# SwirlsV1_1.net
KiCad netlist of a schematic drawn in EAGLE
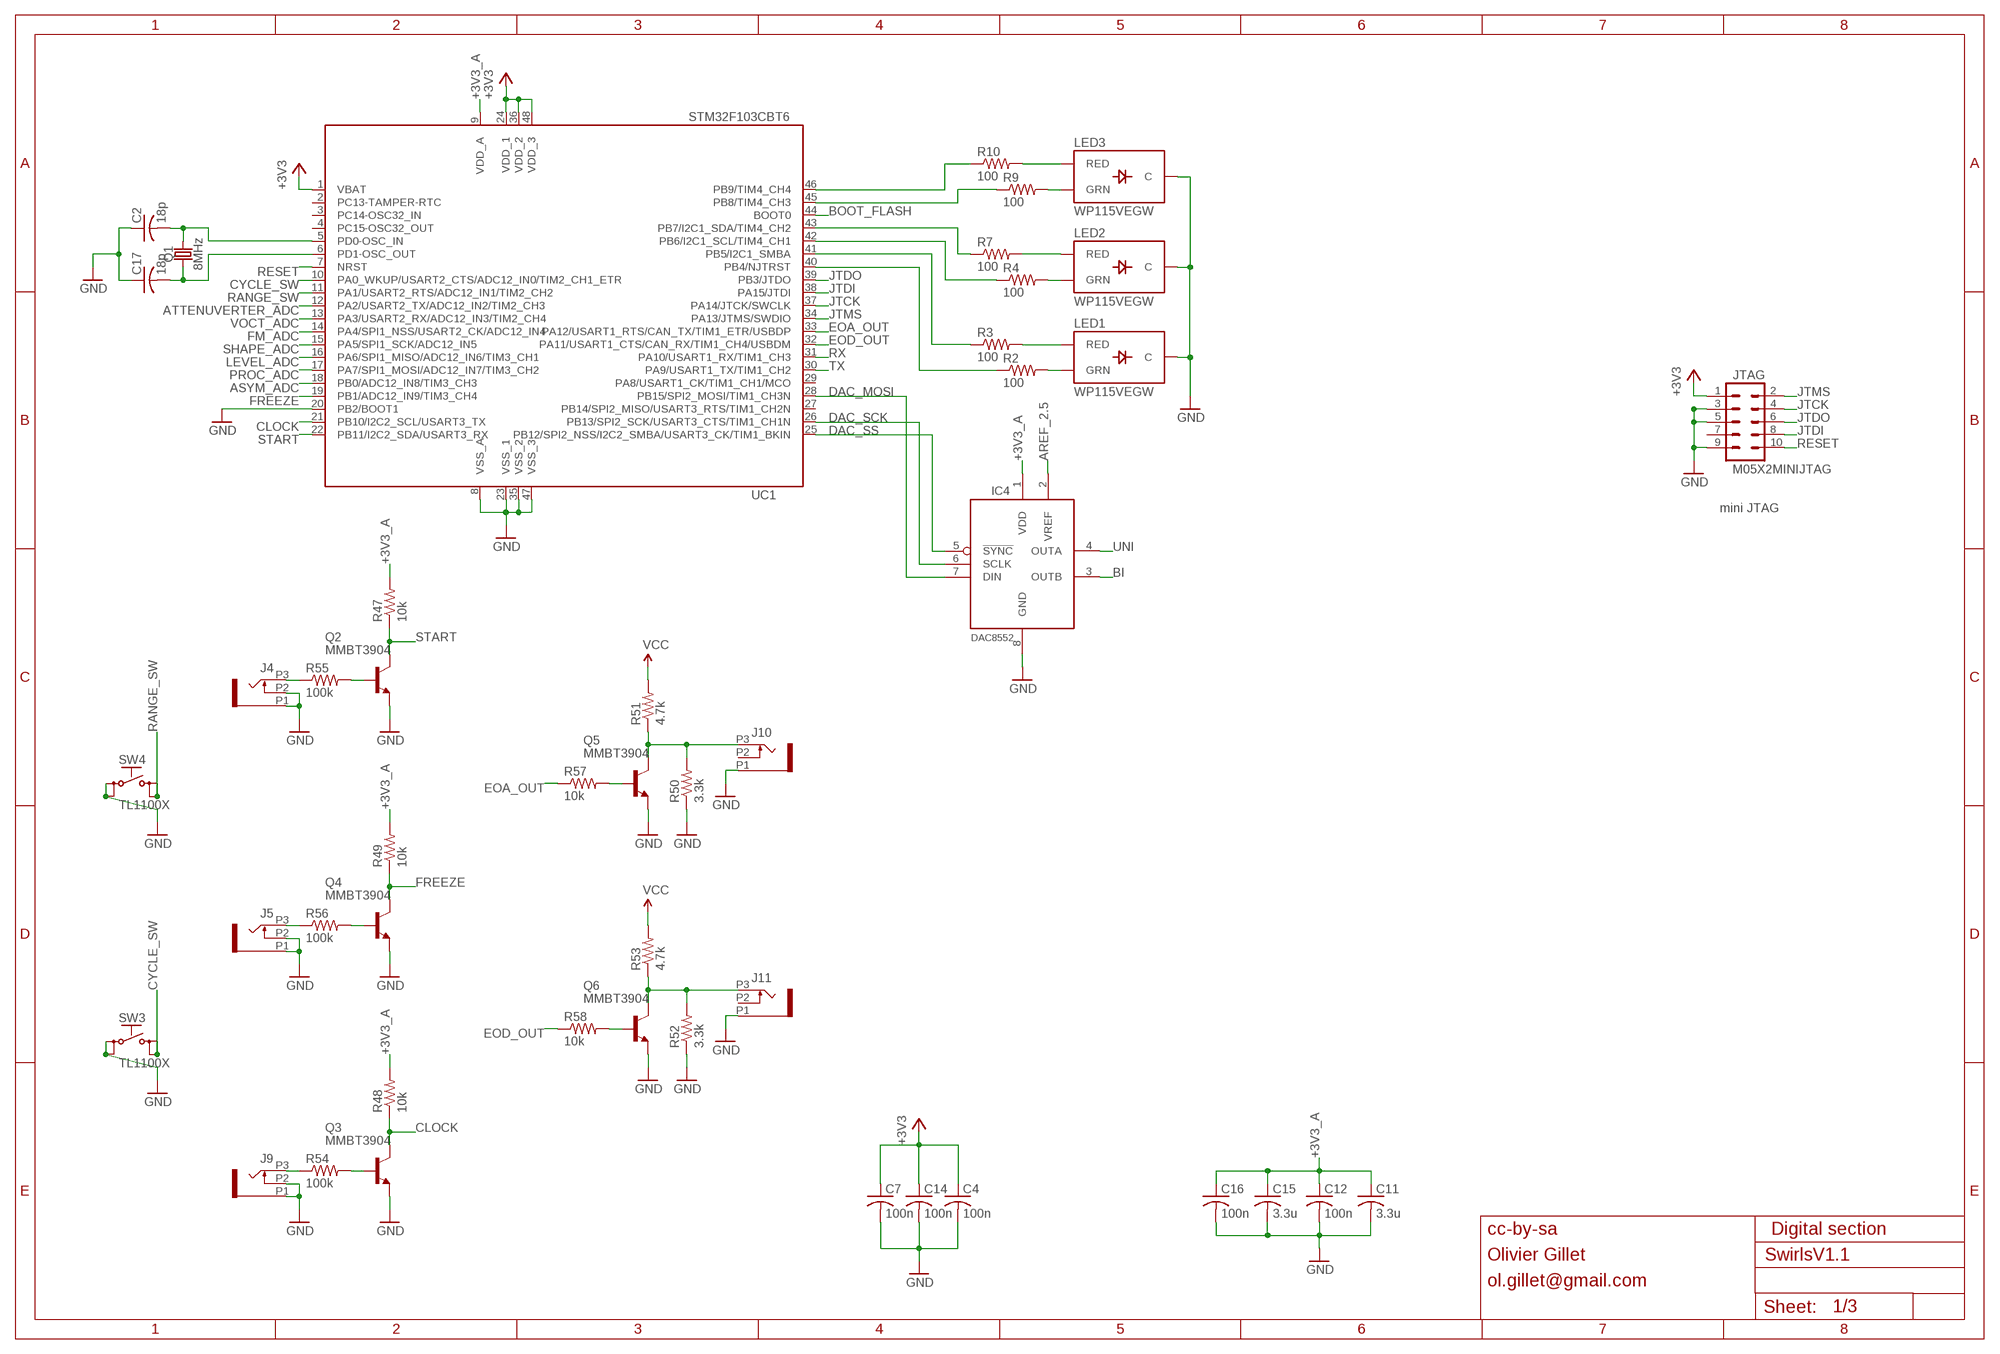
[diagram p0: schematic, sheet 1]
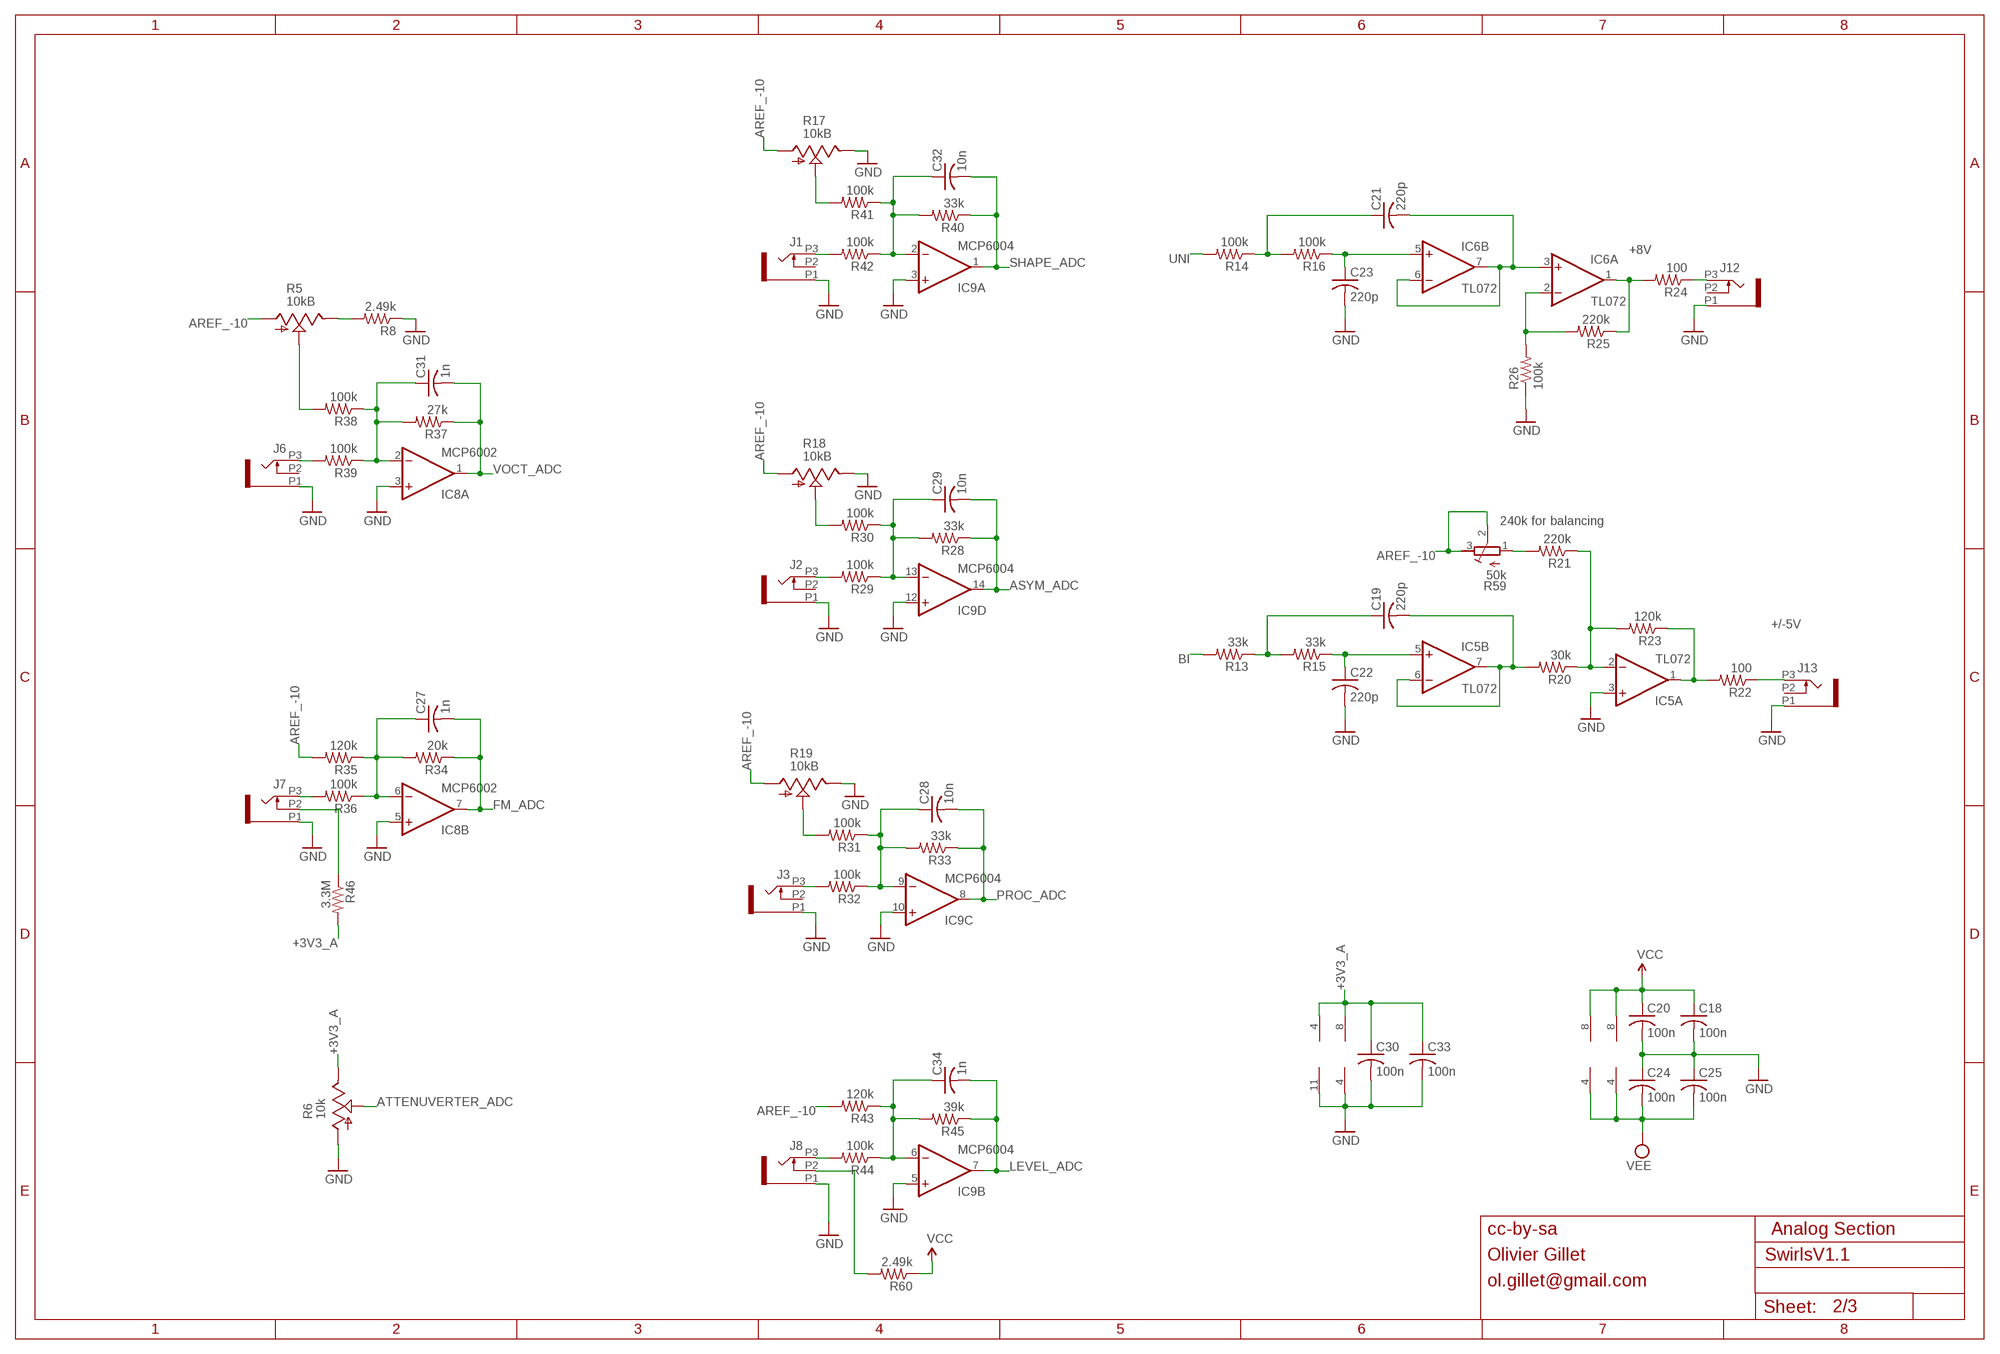
[diagram p1: schematic, sheet 2]
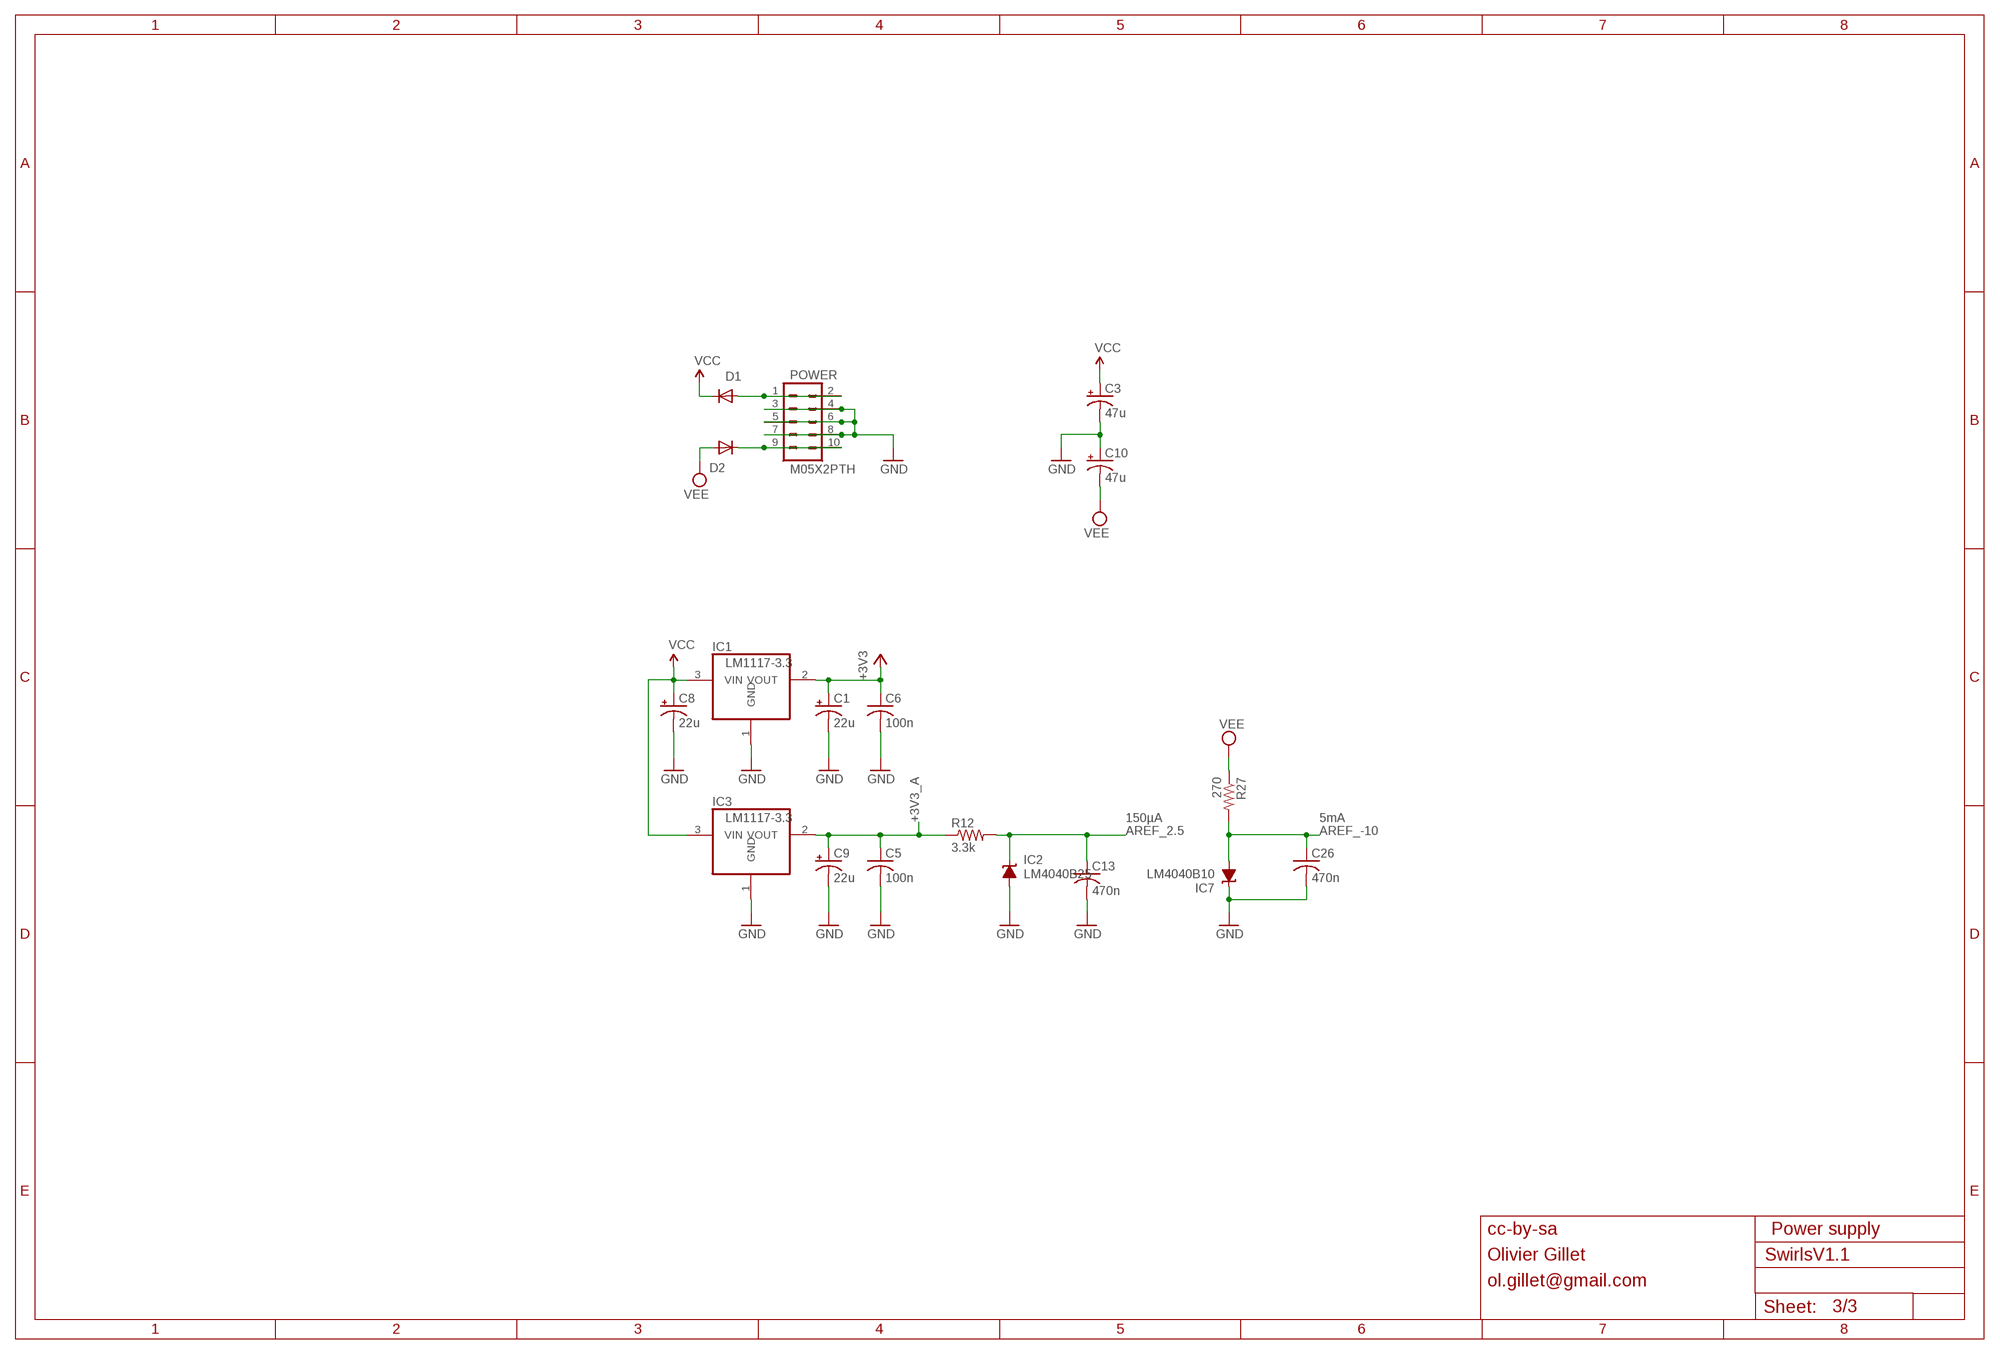
[diagram p2: schematic, sheet 3]

(export (version "E")
  (design (tool "Eeschema 10.0.6"))
  (components
    (comp (ref "C1")
      (value "22u")
      (footprint "eagle-import:PANASONIC_C")
      (libsource (lib "eagle-import") (part "CPOL-USC"))
    )
    (comp (ref "C3")
      (value "47u")
      (footprint "eagle-import:PANASONIC_D")
      (libsource (lib "eagle-import") (part "CPOL-USD"))
    )
    (comp (ref "C5")
      (value "100n")
      (footprint "eagle-import:C0603")
      (libsource (lib "eagle-import") (part "C-USC0603"))
    )
    (comp (ref "C6")
      (value "100n")
      (footprint "eagle-import:C0603")
      (libsource (lib "eagle-import") (part "C-USC0603"))
    )
    (comp (ref "C8")
      (value "22u")
      (footprint "eagle-import:PANASONIC_C")
      (libsource (lib "eagle-import") (part "CPOL-USC"))
    )
    (comp (ref "C9")
      (value "22u")
      (footprint "eagle-import:PANASONIC_C")
      (libsource (lib "eagle-import") (part "CPOL-USC"))
    )
    (comp (ref "C10")
      (value "47u")
      (footprint "eagle-import:PANASONIC_D")
      (libsource (lib "eagle-import") (part "CPOL-USD"))
    )
    (comp (ref "C13")
      (value "470n")
      (footprint "eagle-import:C0603")
      (libsource (lib "eagle-import") (part "C-USC0603"))
    )
    (comp (ref "C26")
      (value "470n")
      (footprint "eagle-import:C0603")
      (libsource (lib "eagle-import") (part "C-USC0603"))
    )
    (comp (ref "D1")
      (value "1N5819HW")
      (footprint "eagle-import:SOD123")
      (libsource (lib "eagle-import") (part "DIODE-SOD123"))
    )
    (comp (ref "D2")
      (value "1N5819HW")
      (footprint "eagle-import:SOD123")
      (libsource (lib "eagle-import") (part "DIODE-SOD123"))
    )
    (comp (ref "IC1")
      (value "LM1117-3.3")
      (footprint "eagle-import:SOT223")
      (libsource (lib "eagle-import") (part "REG1117"))
    )
    (comp (ref "IC2")
      (value "LM4040B25")
      (footprint "eagle-import:DBZ_R-PDSO-G3")
      (libsource (lib "eagle-import") (part "LM4041DBZB12"))
    )
    (comp (ref "IC3")
      (value "LM1117-3.3")
      (footprint "eagle-import:SOT223")
      (libsource (lib "eagle-import") (part "REG1117"))
    )
    (comp (ref "IC7")
      (value "LM4040B10")
      (footprint "eagle-import:DBZ_R-PDSO-G3")
      (libsource (lib "eagle-import") (part "LM4041DBZB12"))
    )
    (comp (ref "POWER")
      (value "M05X2PTH")
      (footprint "eagle-import:AVR_ICSP")
      (libsource (lib "eagle-import") (part "M05X2PTH"))
    )
    (comp (ref "R12")
      (value "3.3k")
      (footprint "eagle-import:R0603")
      (libsource (lib "eagle-import") (part "R-US_R0603"))
    )
    (comp (ref "R27")
      (value "270")
      (footprint "eagle-import:R0603")
      (libsource (lib "eagle-import") (part "R-US_R0603"))
    )
    (comp (ref "C18")
      (value "100n")
      (footprint "eagle-import:C0603")
      (libsource (lib "eagle-import") (part "C-USC0603"))
    )
    (comp (ref "C19")
      (value "220p")
      (footprint "eagle-import:C0603")
      (libsource (lib "eagle-import") (part "C-USC0603"))
    )
    (comp (ref "C20")
      (value "100n")
      (footprint "eagle-import:C0603")
      (libsource (lib "eagle-import") (part "C-USC0603"))
    )
    (comp (ref "C21")
      (value "220p")
      (footprint "eagle-import:C0603")
      (libsource (lib "eagle-import") (part "C-USC0603"))
    )
    (comp (ref "C22")
      (value "220p")
      (footprint "eagle-import:C0603")
      (libsource (lib "eagle-import") (part "C-USC0603"))
    )
    (comp (ref "C23")
      (value "220p")
      (footprint "eagle-import:C0603")
      (libsource (lib "eagle-import") (part "C-USC0603"))
    )
    (comp (ref "C24")
      (value "100n")
      (footprint "eagle-import:C0603")
      (libsource (lib "eagle-import") (part "C-USC0603"))
    )
    (comp (ref "C25")
      (value "100n")
      (footprint "eagle-import:C0603")
      (libsource (lib "eagle-import") (part "C-USC0603"))
    )
    (comp (ref "C27")
      (value "1n")
      (footprint "eagle-import:C0603")
      (libsource (lib "eagle-import") (part "C-USC0603"))
    )
    (comp (ref "C28")
      (value "10n")
      (footprint "eagle-import:C0603")
      (libsource (lib "eagle-import") (part "C-USC0603"))
    )
    (comp (ref "C29")
      (value "10n")
      (footprint "eagle-import:C0603")
      (libsource (lib "eagle-import") (part "C-USC0603"))
    )
    (comp (ref "C30")
      (value "100n")
      (footprint "eagle-import:C0603")
      (libsource (lib "eagle-import") (part "C-USC0603"))
    )
    (comp (ref "C31")
      (value "1n")
      (footprint "eagle-import:C0603")
      (libsource (lib "eagle-import") (part "C-USC0603"))
    )
    (comp (ref "C32")
      (value "10n")
      (footprint "eagle-import:C0603")
      (libsource (lib "eagle-import") (part "C-USC0603"))
    )
    (comp (ref "C33")
      (value "100n")
      (footprint "eagle-import:C0603")
      (libsource (lib "eagle-import") (part "C-USC0603"))
    )
    (comp (ref "C34")
      (value "1n")
      (footprint "eagle-import:C0603")
      (libsource (lib "eagle-import") (part "C-USC0603"))
    )
    (comp (ref "IC5")
      (value "TL072")
      (footprint "eagle-import:TSSOP-8")
      (libsource (lib "eagle-import") (part "TL072TSSOP"))
    )
    (comp (ref "IC6")
      (value "TL072")
      (footprint "eagle-import:TSSOP-8")
      (libsource (lib "eagle-import") (part "TL072TSSOP"))
    )
    (comp (ref "IC8")
      (value "MCP6002")
      (footprint "eagle-import:SO08")
      (libsource (lib "eagle-import") (part "TL072D"))
    )
    (comp (ref "IC9")
      (value "MCP6004")
      (footprint "eagle-import:TSSOP14")
      (libsource (lib "eagle-import") (part "MCP6004ST"))
    )
    (comp (ref "J1")
      (value "PJ301_GUI6")
      (footprint "eagle-import:OG-PJ301_VARIATIONS_WQP_PJ_301M6")
      (libsource (lib "eagle-import") (part "PJ301_GUI6"))
    )
    (comp (ref "J2")
      (value "PJ301_GUI6")
      (footprint "eagle-import:OG-PJ301_VARIATIONS_WQP_PJ_301M6")
      (libsource (lib "eagle-import") (part "PJ301_GUI6"))
    )
    (comp (ref "J3")
      (value "PJ301_GUI6")
      (footprint "eagle-import:OG-PJ301_VARIATIONS_WQP_PJ_301M6")
      (libsource (lib "eagle-import") (part "PJ301_GUI6"))
    )
    (comp (ref "J6")
      (value "PJ301_GUI6")
      (footprint "eagle-import:OG-PJ301_VARIATIONS_WQP_PJ_301M6")
      (libsource (lib "eagle-import") (part "PJ301_GUI6"))
    )
    (comp (ref "J7")
      (value "PJ301_GUI6")
      (footprint "eagle-import:OG-PJ301_VARIATIONS_WQP_PJ_301M6")
      (libsource (lib "eagle-import") (part "PJ301_GUI6"))
    )
    (comp (ref "J8")
      (value "PJ301_GUI6")
      (footprint "eagle-import:OG-PJ301_VARIATIONS_WQP_PJ_301M6")
      (libsource (lib "eagle-import") (part "PJ301_GUI6"))
    )
    (comp (ref "J12")
      (value "PJ301_GUI6")
      (footprint "eagle-import:OG-PJ301_VARIATIONS_WQP_PJ_301M6")
      (libsource (lib "eagle-import") (part "PJ301_GUI6"))
    )
    (comp (ref "J13")
      (value "PJ301_GUI6")
      (footprint "eagle-import:OG-PJ301_VARIATIONS_WQP_PJ_301M6")
      (libsource (lib "eagle-import") (part "PJ301_GUI6"))
    )
    (comp (ref "R5")
      (value "10kB")
      (footprint "eagle-import:ALPS_POT_VERTICAL_PS")
      (libsource (lib "eagle-import") (part "POT_USVERTICAL_PS"))
    )
    (comp (ref "R6")
      (value "10k")
      (footprint "eagle-import:TALLTRIMMER")
      (libsource (lib "eagle-import") (part "POT-ALPS_POT_US"))
    )
    (comp (ref "R8")
      (value "2.49k")
      (footprint "eagle-import:R0603")
      (libsource (lib "eagle-import") (part "R-US_R0603"))
    )
    (comp (ref "R13")
      (value "33k")
      (footprint "eagle-import:R0603")
      (libsource (lib "eagle-import") (part "R-US_R0603"))
    )
    (comp (ref "R14")
      (value "100k")
      (footprint "eagle-import:R0603")
      (libsource (lib "eagle-import") (part "R-US_R0603"))
    )
    (comp (ref "R15")
      (value "33k")
      (footprint "eagle-import:R0603")
      (libsource (lib "eagle-import") (part "R-US_R0603"))
    )
    (comp (ref "R16")
      (value "100k")
      (footprint "eagle-import:R0603")
      (libsource (lib "eagle-import") (part "R-US_R0603"))
    )
    (comp (ref "R17")
      (value "10kB")
      (footprint "eagle-import:TALLTRIMMER")
      (libsource (lib "eagle-import") (part "POT-ALPS_POT_US"))
    )
    (comp (ref "R18")
      (value "10kB")
      (footprint "eagle-import:TALLTRIMMER")
      (libsource (lib "eagle-import") (part "POT-ALPS_POT_US"))
    )
    (comp (ref "R19")
      (value "10kB")
      (footprint "eagle-import:TALLTRIMMER")
      (libsource (lib "eagle-import") (part "POT-ALPS_POT_US"))
    )
    (comp (ref "R20")
      (value "30k")
      (footprint "eagle-import:R0603")
      (libsource (lib "eagle-import") (part "R-US_R0603"))
    )
    (comp (ref "R21")
      (value "220k")
      (footprint "eagle-import:R0603")
      (libsource (lib "eagle-import") (part "R-US_R0603"))
    )
    (comp (ref "R22")
      (value "100")
      (footprint "eagle-import:R0603")
      (libsource (lib "eagle-import") (part "R-US_R0603"))
    )
    (comp (ref "R23")
      (value "120k")
      (footprint "eagle-import:R0603")
      (libsource (lib "eagle-import") (part "R-US_R0603"))
    )
    (comp (ref "R24")
      (value "100")
      (footprint "eagle-import:R0603")
      (libsource (lib "eagle-import") (part "R-US_R0603"))
    )
    (comp (ref "R25")
      (value "220k")
      (footprint "eagle-import:R0603")
      (libsource (lib "eagle-import") (part "R-US_R0603"))
    )
    (comp (ref "R26")
      (value "100k")
      (footprint "eagle-import:R0603")
      (libsource (lib "eagle-import") (part "R-US_R0603"))
    )
    (comp (ref "R28")
      (value "33k")
      (footprint "eagle-import:R0603")
      (libsource (lib "eagle-import") (part "R-US_R0603"))
    )
    (comp (ref "R29")
      (value "100k")
      (footprint "eagle-import:R0603")
      (libsource (lib "eagle-import") (part "R-US_R0603"))
    )
    (comp (ref "R30")
      (value "100k")
      (footprint "eagle-import:R0603")
      (libsource (lib "eagle-import") (part "R-US_R0603"))
    )
    (comp (ref "R31")
      (value "100k")
      (footprint "eagle-import:R0603")
      (libsource (lib "eagle-import") (part "R-US_R0603"))
    )
    (comp (ref "R32")
      (value "100k")
      (footprint "eagle-import:R0603")
      (libsource (lib "eagle-import") (part "R-US_R0603"))
    )
    (comp (ref "R33")
      (value "33k")
      (footprint "eagle-import:R0603")
      (libsource (lib "eagle-import") (part "R-US_R0603"))
    )
    (comp (ref "R34")
      (value "20k")
      (footprint "eagle-import:R0603")
      (libsource (lib "eagle-import") (part "R-US_R0603"))
    )
    (comp (ref "R35")
      (value "120k")
      (footprint "eagle-import:R0603")
      (libsource (lib "eagle-import") (part "R-US_R0603"))
    )
    (comp (ref "R36")
      (value "100k")
      (footprint "eagle-import:R0603")
      (libsource (lib "eagle-import") (part "R-US_R0603"))
    )
    (comp (ref "R37")
      (value "27k")
      (footprint "eagle-import:R0603")
      (libsource (lib "eagle-import") (part "R-US_R0603"))
    )
    (comp (ref "R38")
      (value "100k")
      (footprint "eagle-import:R0603")
      (libsource (lib "eagle-import") (part "R-US_R0603"))
    )
    (comp (ref "R39")
      (value "100k")
      (footprint "eagle-import:R0603")
      (libsource (lib "eagle-import") (part "R-US_R0603"))
    )
    (comp (ref "R40")
      (value "33k")
      (footprint "eagle-import:R0603")
      (libsource (lib "eagle-import") (part "R-US_R0603"))
    )
    (comp (ref "R41")
      (value "100k")
      (footprint "eagle-import:R0603")
      (libsource (lib "eagle-import") (part "R-US_R0603"))
    )
    (comp (ref "R42")
      (value "100k")
      (footprint "eagle-import:R0603")
      (libsource (lib "eagle-import") (part "R-US_R0603"))
    )
    (comp (ref "R43")
      (value "120k")
      (footprint "eagle-import:R0603")
      (libsource (lib "eagle-import") (part "R-US_R0603"))
    )
    (comp (ref "R44")
      (value "100k")
      (footprint "eagle-import:R0603")
      (libsource (lib "eagle-import") (part "R-US_R0603"))
    )
    (comp (ref "R45")
      (value "39k")
      (footprint "eagle-import:R0603")
      (libsource (lib "eagle-import") (part "R-US_R0603"))
    )
    (comp (ref "R46")
      (value "3.3M")
      (footprint "eagle-import:R0603")
      (libsource (lib "eagle-import") (part "R-US_R0603"))
    )
    (comp (ref "R59")
      (value "50k")
      (footprint "eagle-import:RTRIM3296W")
      (libsource (lib "eagle-import") (part "R-TRIMM3296W"))
    )
    (comp (ref "R60")
      (value "2.49k")
      (footprint "eagle-import:R0805")
      (libsource (lib "eagle-import") (part "R-US_R0805"))
    )
    (comp (ref "C2")
      (value "18p")
      (footprint "eagle-import:C0603")
      (libsource (lib "eagle-import") (part "C-USC0603"))
    )
    (comp (ref "C4")
      (value "100n")
      (footprint "eagle-import:C0603")
      (libsource (lib "eagle-import") (part "C-USC0603"))
    )
    (comp (ref "C7")
      (value "100n")
      (footprint "eagle-import:C0603")
      (libsource (lib "eagle-import") (part "C-USC0603"))
    )
    (comp (ref "C11")
      (value "3.3u")
      (footprint "eagle-import:C0603")
      (libsource (lib "eagle-import") (part "C-USC0603"))
    )
    (comp (ref "C12")
      (value "100n")
      (footprint "eagle-import:C0603")
      (libsource (lib "eagle-import") (part "C-USC0603"))
    )
    (comp (ref "C14")
      (value "100n")
      (footprint "eagle-import:C0603")
      (libsource (lib "eagle-import") (part "C-USC0603"))
    )
    (comp (ref "C15")
      (value "3.3u")
      (footprint "eagle-import:C0603")
      (libsource (lib "eagle-import") (part "C-USC0603"))
    )
    (comp (ref "C16")
      (value "100n")
      (footprint "eagle-import:C0603")
      (libsource (lib "eagle-import") (part "C-USC0603"))
    )
    (comp (ref "C17")
      (value "18p")
      (footprint "eagle-import:C0603")
      (libsource (lib "eagle-import") (part "C-USC0603"))
    )
    (comp (ref "IC4")
      (value "DAC8552")
      (footprint "eagle-import:MSOP-8")
      (libsource (lib "eagle-import") (part "DAC8552"))
    )
    (comp (ref "J4")
      (value "PJ301_GUI6")
      (footprint "eagle-import:OG-PJ301_VARIATIONS_WQP_PJ_301M6")
      (libsource (lib "eagle-import") (part "PJ301_GUI6"))
    )
    (comp (ref "J5")
      (value "PJ301_GUI6")
      (footprint "eagle-import:OG-PJ301_VARIATIONS_WQP_PJ_301M6")
      (libsource (lib "eagle-import") (part "PJ301_GUI6"))
    )
    (comp (ref "J9")
      (value "PJ301_GUI6")
      (footprint "eagle-import:OG-PJ301_VARIATIONS_WQP_PJ_301M6")
      (libsource (lib "eagle-import") (part "PJ301_GUI6"))
    )
    (comp (ref "J10")
      (value "PJ301_GUI6")
      (footprint "eagle-import:OG-PJ301_VARIATIONS_WQP_PJ_301M6")
      (libsource (lib "eagle-import") (part "PJ301_GUI6"))
    )
    (comp (ref "J11")
      (value "PJ301_GUI6")
      (footprint "eagle-import:OG-PJ301_VARIATIONS_WQP_PJ_301M6")
      (libsource (lib "eagle-import") (part "PJ301_GUI6"))
    )
    (comp (ref "JTAG")
      (value "M05X2MINIJTAG")
      (footprint "eagle-import:2X5-1.27")
      (libsource (lib "eagle-import") (part "M05X2MINIJTAG"))
    )
    (comp (ref "LED1")
      (value "WP115VEGW")
      (footprint "eagle-import:LED-BICOLOR-THROUGHHOLE")
      (libsource (lib "eagle-import") (part "LED-BICOLOR-THROUGHHOLE"))
    )
    (comp (ref "LED2")
      (value "WP115VEGW")
      (footprint "eagle-import:LED-BICOLOR-THROUGHHOLE")
      (libsource (lib "eagle-import") (part "LED-BICOLOR-THROUGHHOLE"))
    )
    (comp (ref "LED3")
      (value "WP115VEGW")
      (footprint "eagle-import:LED-BICOLOR-THROUGHHOLE")
      (libsource (lib "eagle-import") (part "LED-BICOLOR-THROUGHHOLE"))
    )
    (comp (ref "Q1")
      (value "8MHz")
      (footprint "eagle-import:HC49UP")
      (libsource (lib "eagle-import") (part "CRYSTAL-8MHZSMD-HC49UP"))
    )
    (comp (ref "Q2")
      (value "MMBT3904")
      (footprint "eagle-import:SOT23-BEC")
      (libsource (lib "eagle-import") (part "-NPN-SOT23-BECMMBT3904LT1"))
    )
    (comp (ref "Q3")
      (value "MMBT3904")
      (footprint "eagle-import:SOT23-BEC")
      (libsource (lib "eagle-import") (part "-NPN-SOT23-BECMMBT3904LT1"))
    )
    (comp (ref "Q4")
      (value "MMBT3904")
      (footprint "eagle-import:SOT23-BEC")
      (libsource (lib "eagle-import") (part "-NPN-SOT23-BECMMBT3904LT1"))
    )
    (comp (ref "Q5")
      (value "MMBT3904")
      (footprint "eagle-import:SOT23-BEC")
      (libsource (lib "eagle-import") (part "-NPN-SOT23-BECMMBT3904LT1"))
    )
    (comp (ref "Q6")
      (value "MMBT3904")
      (footprint "eagle-import:SOT23-BEC")
      (libsource (lib "eagle-import") (part "-NPN-SOT23-BECMMBT3904LT1"))
    )
    (comp (ref "R2")
      (value "100")
      (footprint "eagle-import:R0603")
      (libsource (lib "eagle-import") (part "R-US_R0603"))
    )
    (comp (ref "R3")
      (value "100")
      (footprint "eagle-import:R0603")
      (libsource (lib "eagle-import") (part "R-US_R0603"))
    )
    (comp (ref "R4")
      (value "100")
      (footprint "eagle-import:R0603")
      (libsource (lib "eagle-import") (part "R-US_R0603"))
    )
    (comp (ref "R7")
      (value "100")
      (footprint "eagle-import:R0603")
      (libsource (lib "eagle-import") (part "R-US_R0603"))
    )
    (comp (ref "R9")
      (value "100")
      (footprint "eagle-import:R0603")
      (libsource (lib "eagle-import") (part "R-US_R0603"))
    )
    (comp (ref "R10")
      (value "100")
      (footprint "eagle-import:R0603")
      (libsource (lib "eagle-import") (part "R-US_R0603"))
    )
    (comp (ref "R47")
      (value "10k")
      (footprint "eagle-import:R0603")
      (libsource (lib "eagle-import") (part "R-US_R0603"))
    )
    (comp (ref "R48")
      (value "10k")
      (footprint "eagle-import:R0603")
      (libsource (lib "eagle-import") (part "R-US_R0603"))
    )
    (comp (ref "R49")
      (value "10k")
      (footprint "eagle-import:R0603")
      (libsource (lib "eagle-import") (part "R-US_R0603"))
    )
    (comp (ref "R50")
      (value "3.3k")
      (footprint "eagle-import:R0603")
      (libsource (lib "eagle-import") (part "R-US_R0603"))
    )
    (comp (ref "R51")
      (value "4.7k")
      (footprint "eagle-import:R0603")
      (libsource (lib "eagle-import") (part "R-US_R0603"))
    )
    (comp (ref "R52")
      (value "3.3k")
      (footprint "eagle-import:R0603")
      (libsource (lib "eagle-import") (part "R-US_R0603"))
    )
    (comp (ref "R53")
      (value "4.7k")
      (footprint "eagle-import:R0603")
      (libsource (lib "eagle-import") (part "R-US_R0603"))
    )
    (comp (ref "R54")
      (value "100k")
      (footprint "eagle-import:R0603")
      (libsource (lib "eagle-import") (part "R-US_R0603"))
    )
    (comp (ref "R55")
      (value "100k")
      (footprint "eagle-import:R0603")
      (libsource (lib "eagle-import") (part "R-US_R0603"))
    )
    (comp (ref "R56")
      (value "100k")
      (footprint "eagle-import:R0603")
      (libsource (lib "eagle-import") (part "R-US_R0603"))
    )
    (comp (ref "R57")
      (value "10k")
      (footprint "eagle-import:R0603")
      (libsource (lib "eagle-import") (part "R-US_R0603"))
    )
    (comp (ref "R58")
      (value "10k")
      (footprint "eagle-import:R0603")
      (libsource (lib "eagle-import") (part "R-US_R0603"))
    )
    (comp (ref "SW3")
      (value "TL1100X")
      (footprint "eagle-import:TL1100X")
      (libsource (lib "eagle-import") (part "TL1100X"))
    )
    (comp (ref "SW4")
      (value "TL1100X")
      (footprint "eagle-import:TL1100X")
      (libsource (lib "eagle-import") (part "TL1100X"))
    )
    (comp (ref "UC1")
      (value "STM32F103CBT6")
      (footprint "eagle-import:LQFP48")
      (libsource (lib "eagle-import") (part "STM32F103CB"))
    )
  )
  (nets
    (net (code "1") (name "+3V3") (class "Default")
      (node (ref "C1") (pin "+") (pinfunction "+_+") (pintype "passive"))
      (node (ref "C14") (pin "1") (pinfunction "1_1") (pintype "passive"))
      (node (ref "C4") (pin "1") (pinfunction "1_1") (pintype "passive"))
      (node (ref "C6") (pin "1") (pinfunction "1_1") (pintype "passive"))
      (node (ref "C7") (pin "1") (pinfunction "1_1") (pintype "passive"))
      (node (ref "IC1") (pin "2") (pinfunction "VOUT_2") (pintype "output"))
      (node (ref "JTAG") (pin "1") (pinfunction "1_1") (pintype "passive"))
      (node (ref "UC1") (pin "1") (pinfunction "VBAT_1") (pintype "power_in"))
      (node (ref "UC1") (pin "24") (pinfunction "VDD_1_24") (pintype "power_in"))
      (node (ref "UC1") (pin "36") (pinfunction "VDD_2_36") (pintype "power_in"))
      (node (ref "UC1") (pin "48") (pinfunction "VDD_3_48") (pintype "power_in"))
    )
    (net (code "2") (name "+3V3_A") (class "Default")
      (node (ref "C11") (pin "1") (pinfunction "1_1") (pintype "passive"))
      (node (ref "C12") (pin "1") (pinfunction "1_1") (pintype "passive"))
      (node (ref "C15") (pin "1") (pinfunction "1_1") (pintype "passive"))
      (node (ref "C16") (pin "1") (pinfunction "1_1") (pintype "passive"))
      (node (ref "C30") (pin "1") (pinfunction "1_1") (pintype "passive"))
      (node (ref "C33") (pin "1") (pinfunction "1_1") (pintype "passive"))
      (node (ref "C5") (pin "1") (pinfunction "1_1") (pintype "passive"))
      (node (ref "C9") (pin "+") (pinfunction "+_+") (pintype "passive"))
      (node (ref "IC3") (pin "2") (pinfunction "VOUT_2") (pintype "output"))
      (node (ref "IC4") (pin "1") (pinfunction "VDD_1") (pintype "power_in"))
      (node (ref "IC8") (pin "8") (pinfunction "V+_8") (pintype "power_in"))
      (node (ref "IC9") (pin "4") (pinfunction "V+_4") (pintype "power_in"))
      (node (ref "R12") (pin "1") (pinfunction "1_1") (pintype "passive"))
      (node (ref "R46") (pin "2") (pinfunction "2_2") (pintype "passive"))
      (node (ref "R47") (pin "2") (pinfunction "2_2") (pintype "passive"))
      (node (ref "R48") (pin "2") (pinfunction "2_2") (pintype "passive"))
      (node (ref "R49") (pin "2") (pinfunction "2_2") (pintype "passive"))
      (node (ref "R6") (pin "P$1") (pinfunction "E_P$1") (pintype "passive"))
      (node (ref "UC1") (pin "9") (pinfunction "VDD_A_9") (pintype "power_in"))
    )
    (net (code "3") (name "AREF_-10") (class "Default")
      (node (ref "C26") (pin "1") (pinfunction "1_1") (pintype "passive"))
      (node (ref "IC7") (pin "2") (pinfunction "A_2") (pintype "passive"))
      (node (ref "R17") (pin "P$3") (pinfunction "A_P$3") (pintype "passive"))
      (node (ref "R18") (pin "P$3") (pinfunction "A_P$3") (pintype "passive"))
      (node (ref "R19") (pin "P$3") (pinfunction "A_P$3") (pintype "passive"))
      (node (ref "R27") (pin "2") (pinfunction "2_2") (pintype "passive"))
      (node (ref "R35") (pin "2") (pinfunction "2_2") (pintype "passive"))
      (node (ref "R43") (pin "2") (pinfunction "2_2") (pintype "passive"))
      (node (ref "R5") (pin "P$3") (pinfunction "A_P$3") (pintype "passive"))
      (node (ref "R59") (pin "2") (pinfunction "S_2") (pintype "passive"))
      (node (ref "R59") (pin "3") (pinfunction "E_3") (pintype "passive"))
    )
    (net (code "4") (name "AREF_2.5") (class "Default")
      (node (ref "C13") (pin "1") (pinfunction "1_1") (pintype "passive"))
      (node (ref "IC2") (pin "1") (pinfunction "C_1") (pintype "passive"))
      (node (ref "IC4") (pin "2") (pinfunction "VREF_2") (pintype "power_in"))
      (node (ref "R12") (pin "2") (pinfunction "2_2") (pintype "passive"))
    )
    (net (code "5") (name "ASYM_ADC") (class "Default")
      (node (ref "C29") (pin "2") (pinfunction "2_2") (pintype "passive"))
      (node (ref "IC9") (pin "14") (pinfunction "OUT_14") (pintype "output"))
      (node (ref "R28") (pin "1") (pinfunction "1_1") (pintype "passive"))
      (node (ref "UC1") (pin "18") (pinfunction "PB0/ADC12_IN8/TIM3_CH3_18") (pintype "bidirectional"))
    )
    (net (code "6") (name "ATTENUVERTER_ADC") (class "Default")
      (node (ref "R6") (pin "P$2") (pinfunction "S_P$2") (pintype "passive"))
      (node (ref "UC1") (pin "12") (pinfunction "PA2/USART2_TX/ADC12_IN2/TIM2_CH3_12") (pintype "bidirectional"))
    )
    (net (code "7") (name "BI") (class "Default")
      (node (ref "IC4") (pin "3") (pinfunction "OUTB_3") (pintype "input"))
      (node (ref "R13") (pin "2") (pinfunction "2_2") (pintype "passive"))
    )
    (net (code "8") (name "BOOT_FLASH") (class "Default")
      (node (ref "UC1") (pin "44") (pinfunction "BOOT0_44") (pintype "input"))
    )
    (net (code "9") (name "CLOCK") (class "Default")
      (node (ref "Q3") (pin "C") (pinfunction "C_C") (pintype "passive"))
      (node (ref "R48") (pin "1") (pinfunction "1_1") (pintype "passive"))
      (node (ref "UC1") (pin "21") (pinfunction "PB10/I2C2_SCL/USART3_TX_21") (pintype "input"))
    )
    (net (code "10") (name "CYCLE_SW") (class "Default")
      (node (ref "SW3") (pin "3") (pinfunction "S_3") (pintype "passive"))
      (node (ref "SW3") (pin "4") (pinfunction "S1_4") (pintype "passive"))
      (node (ref "UC1") (pin "10") (pinfunction "PA0_WKUP/USART2_CTS/ADC12_IN0/TIM2_CH1_ETR_10") (pintype "bidirectional"))
    )
    (net (code "11") (name "DAC_MOSI") (class "Default")
      (node (ref "IC4") (pin "7") (pinfunction "DIN_7") (pintype "bidirectional"))
      (node (ref "UC1") (pin "28") (pinfunction "PB15/SPI2_MOSI/TIM1_CH3N_28") (pintype "input"))
    )
    (net (code "12") (name "DAC_SCK") (class "Default")
      (node (ref "IC4") (pin "6") (pinfunction "SCLK_6") (pintype "bidirectional"))
      (node (ref "UC1") (pin "26") (pinfunction "PB13/SPI2_SCK/USART3_CTS/TIM1_CH1N_26") (pintype "input"))
    )
    (net (code "13") (name "DAC_SS") (class "Default")
      (node (ref "IC4") (pin "5") (pinfunction "~{SYNC}_5") (pintype "bidirectional"))
      (node (ref "UC1") (pin "25") (pinfunction "PB12/SPI2_NSS/I2C2_SMBA/USART3_CK/TIM1_BKIN_25") (pintype "input"))
    )
    (net (code "14") (name "EOA_OUT") (class "Default")
      (node (ref "R57") (pin "1") (pinfunction "1_1") (pintype "passive"))
      (node (ref "UC1") (pin "33") (pinfunction "PA12/USART1_RTS/CAN_TX/TIM1_ETR/USBDP_33") (pintype "bidirectional"))
    )
    (net (code "15") (name "EOD_OUT") (class "Default")
      (node (ref "R58") (pin "1") (pinfunction "1_1") (pintype "passive"))
      (node (ref "UC1") (pin "32") (pinfunction "PA11/USART1_CTS/CAN_RX/TIM1_CH4/USBDM_32") (pintype "bidirectional"))
    )
    (net (code "16") (name "FM_ADC") (class "Default")
      (node (ref "C27") (pin "2") (pinfunction "2_2") (pintype "passive"))
      (node (ref "IC8") (pin "7") (pinfunction "OUT_7") (pintype "output"))
      (node (ref "R34") (pin "1") (pinfunction "1_1") (pintype "passive"))
      (node (ref "UC1") (pin "14") (pinfunction "PA4/SPI1_NSS/USART2_CK/ADC12_IN4_14") (pintype "bidirectional"))
    )
    (net (code "17") (name "FREEZE") (class "Default")
      (node (ref "Q4") (pin "C") (pinfunction "C_C") (pintype "passive"))
      (node (ref "R49") (pin "1") (pinfunction "1_1") (pintype "passive"))
      (node (ref "UC1") (pin "19") (pinfunction "PB1/ADC12_IN9/TIM3_CH4_19") (pintype "bidirectional"))
    )
    (net (code "18") (name "GND") (class "Default")
      (node (ref "C1") (pin "-") (pinfunction "-_-") (pintype "passive"))
      (node (ref "C10") (pin "+") (pinfunction "+_+") (pintype "passive"))
      (node (ref "C11") (pin "2") (pinfunction "2_2") (pintype "passive"))
      (node (ref "C12") (pin "2") (pinfunction "2_2") (pintype "passive"))
      (node (ref "C13") (pin "2") (pinfunction "2_2") (pintype "passive"))
      (node (ref "C14") (pin "2") (pinfunction "2_2") (pintype "passive"))
      (node (ref "C15") (pin "2") (pinfunction "2_2") (pintype "passive"))
      (node (ref "C16") (pin "2") (pinfunction "2_2") (pintype "passive"))
      (node (ref "C17") (pin "1") (pinfunction "1_1") (pintype "passive"))
      (node (ref "C18") (pin "2") (pinfunction "2_2") (pintype "passive"))
      (node (ref "C2") (pin "1") (pinfunction "1_1") (pintype "passive"))
      (node (ref "C20") (pin "2") (pinfunction "2_2") (pintype "passive"))
      (node (ref "C22") (pin "2") (pinfunction "2_2") (pintype "passive"))
      (node (ref "C23") (pin "2") (pinfunction "2_2") (pintype "passive"))
      (node (ref "C24") (pin "1") (pinfunction "1_1") (pintype "passive"))
      (node (ref "C25") (pin "1") (pinfunction "1_1") (pintype "passive"))
      (node (ref "C26") (pin "2") (pinfunction "2_2") (pintype "passive"))
      (node (ref "C3") (pin "-") (pinfunction "-_-") (pintype "passive"))
      (node (ref "C30") (pin "2") (pinfunction "2_2") (pintype "passive"))
      (node (ref "C33") (pin "2") (pinfunction "2_2") (pintype "passive"))
      (node (ref "C4") (pin "2") (pinfunction "2_2") (pintype "passive"))
      (node (ref "C5") (pin "2") (pinfunction "2_2") (pintype "passive"))
      (node (ref "C6") (pin "2") (pinfunction "2_2") (pintype "passive"))
      (node (ref "C7") (pin "2") (pinfunction "2_2") (pintype "passive"))
      (node (ref "C8") (pin "-") (pinfunction "-_-") (pintype "passive"))
      (node (ref "C9") (pin "-") (pinfunction "-_-") (pintype "passive"))
      (node (ref "IC1") (pin "1") (pinfunction "GND_1") (pintype "power_in"))
      (node (ref "IC2") (pin "2") (pinfunction "A_2") (pintype "passive"))
      (node (ref "IC3") (pin "1") (pinfunction "GND_1") (pintype "power_in"))
      (node (ref "IC4") (pin "8") (pinfunction "GND_8") (pintype "power_in"))
      (node (ref "IC5") (pin "3") (pinfunction "+IN_3") (pintype "input"))
      (node (ref "IC7") (pin "1") (pinfunction "C_1") (pintype "passive"))
      (node (ref "IC8") (pin "3") (pinfunction "+IN_3") (pintype "input"))
      (node (ref "IC8") (pin "4") (pinfunction "V-_4") (pintype "power_in"))
      (node (ref "IC8") (pin "5") (pinfunction "+IN_5") (pintype "input"))
      (node (ref "IC9") (pin "10") (pinfunction "+IN_10") (pintype "input"))
      (node (ref "IC9") (pin "11") (pinfunction "V-_11") (pintype "power_in"))
      (node (ref "IC9") (pin "12") (pinfunction "+IN_12") (pintype "input"))
      (node (ref "IC9") (pin "3") (pinfunction "+IN_3") (pintype "input"))
      (node (ref "IC9") (pin "5") (pinfunction "+IN_5") (pintype "input"))
      (node (ref "J1") (pin "P1") (pinfunction "1_P1") (pintype "passive"))
      (node (ref "J10") (pin "P1") (pinfunction "1_P1") (pintype "passive"))
      (node (ref "J11") (pin "P1") (pinfunction "1_P1") (pintype "passive"))
      (node (ref "J12") (pin "P1") (pinfunction "1_P1") (pintype "passive"))
      (node (ref "J13") (pin "P1") (pinfunction "1_P1") (pintype "passive"))
      (node (ref "J2") (pin "P1") (pinfunction "1_P1") (pintype "passive"))
      (node (ref "J3") (pin "P1") (pinfunction "1_P1") (pintype "passive"))
      (node (ref "J4") (pin "P1") (pinfunction "1_P1") (pintype "passive"))
      (node (ref "J4") (pin "P2") (pinfunction "2_P2") (pintype "passive"))
      (node (ref "J5") (pin "P1") (pinfunction "1_P1") (pintype "passive"))
      (node (ref "J5") (pin "P2") (pinfunction "2_P2") (pintype "passive"))
      (node (ref "J6") (pin "P1") (pinfunction "1_P1") (pintype "passive"))
      (node (ref "J7") (pin "P1") (pinfunction "1_P1") (pintype "passive"))
      (node (ref "J8") (pin "P1") (pinfunction "1_P1") (pintype "passive"))
      (node (ref "J9") (pin "P1") (pinfunction "1_P1") (pintype "passive"))
      (node (ref "J9") (pin "P2") (pinfunction "2_P2") (pintype "passive"))
      (node (ref "JTAG") (pin "3") (pinfunction "3_3") (pintype "passive"))
      (node (ref "JTAG") (pin "5") (pinfunction "5_5") (pintype "passive"))
      (node (ref "JTAG") (pin "9") (pinfunction "9_9") (pintype "passive"))
      (node (ref "LED1") (pin "2") (pinfunction "C_2") (pintype "bidirectional"))
      (node (ref "LED2") (pin "2") (pinfunction "C_2") (pintype "bidirectional"))
      (node (ref "LED3") (pin "2") (pinfunction "C_2") (pintype "bidirectional"))
      (node (ref "POWER") (pin "3") (pinfunction "3_3") (pintype "passive"))
      (node (ref "POWER") (pin "4") (pinfunction "4_4") (pintype "passive"))
      (node (ref "POWER") (pin "5") (pinfunction "5_5") (pintype "passive"))
      (node (ref "POWER") (pin "6") (pinfunction "6_6") (pintype "passive"))
      (node (ref "POWER") (pin "7") (pinfunction "7_7") (pintype "passive"))
      (node (ref "POWER") (pin "8") (pinfunction "8_8") (pintype "passive"))
      (node (ref "Q2") (pin "E") (pinfunction "E_E") (pintype "passive"))
      (node (ref "Q3") (pin "E") (pinfunction "E_E") (pintype "passive"))
      (node (ref "Q4") (pin "E") (pinfunction "E_E") (pintype "passive"))
      (node (ref "Q5") (pin "E") (pinfunction "E_E") (pintype "passive"))
      (node (ref "Q6") (pin "E") (pinfunction "E_E") (pintype "passive"))
      (node (ref "R17") (pin "P$1") (pinfunction "E_P$1") (pintype "passive"))
      (node (ref "R18") (pin "P$1") (pinfunction "E_P$1") (pintype "passive"))
      (node (ref "R19") (pin "P$1") (pinfunction "E_P$1") (pintype "passive"))
      (node (ref "R26") (pin "1") (pinfunction "1_1") (pintype "passive"))
      (node (ref "R50") (pin "1") (pinfunction "1_1") (pintype "passive"))
      (node (ref "R52") (pin "1") (pinfunction "1_1") (pintype "passive"))
      (node (ref "R6") (pin "P$3") (pinfunction "A_P$3") (pintype "passive"))
      (node (ref "R8") (pin "1") (pinfunction "1_1") (pintype "passive"))
      (node (ref "SW3") (pin "1") (pinfunction "P_1") (pintype "passive"))
      (node (ref "SW3") (pin "2") (pinfunction "P1_2") (pintype "passive"))
      (node (ref "SW4") (pin "1") (pinfunction "P_1") (pintype "passive"))
      (node (ref "SW4") (pin "2") (pinfunction "P1_2") (pintype "passive"))
      (node (ref "UC1") (pin "20") (pinfunction "PB2/BOOT1_20") (pintype "bidirectional"))
      (node (ref "UC1") (pin "23") (pinfunction "VSS_1_23") (pintype "power_in"))
      (node (ref "UC1") (pin "35") (pinfunction "VSS_2_35") (pintype "power_in"))
      (node (ref "UC1") (pin "47") (pinfunction "VSS_3_47") (pintype "power_in"))
      (node (ref "UC1") (pin "8") (pinfunction "VSS_A_8") (pintype "power_in"))
    )
    (net (code "19") (name "JTCK") (class "Default")
      (node (ref "JTAG") (pin "4") (pinfunction "4_4") (pintype "passive"))
      (node (ref "UC1") (pin "37") (pinfunction "PA14/JTCK/SWCLK_37") (pintype "bidirectional"))
    )
    (net (code "20") (name "JTDI") (class "Default")
      (node (ref "JTAG") (pin "8") (pinfunction "8_8") (pintype "passive"))
      (node (ref "UC1") (pin "38") (pinfunction "PA15/JTDI_38") (pintype "bidirectional"))
    )
    (net (code "21") (name "JTDO") (class "Default")
      (node (ref "JTAG") (pin "6") (pinfunction "6_6") (pintype "passive"))
      (node (ref "UC1") (pin "39") (pinfunction "PB3/JTDO_39") (pintype "bidirectional"))
    )
    (net (code "22") (name "JTMS") (class "Default")
      (node (ref "JTAG") (pin "2") (pinfunction "2_2") (pintype "passive"))
      (node (ref "UC1") (pin "34") (pinfunction "PA13/JTMS/SWDIO_34") (pintype "bidirectional"))
    )
    (net (code "23") (name "LEVEL_ADC") (class "Default")
      (node (ref "C34") (pin "2") (pinfunction "2_2") (pintype "passive"))
      (node (ref "IC9") (pin "7") (pinfunction "OUT_7") (pintype "output"))
      (node (ref "R45") (pin "1") (pinfunction "1_1") (pintype "passive"))
      (node (ref "UC1") (pin "16") (pinfunction "PA6/SPI1_MISO/ADC12_IN6/TIM3_CH1_16") (pintype "bidirectional"))
    )
    (net (code "24") (name "Net-(C19-Pad1)") (class "Default")
      (node (ref "C19") (pin "1") (pinfunction "1_1") (pintype "passive"))
      (node (ref "R13") (pin "1") (pinfunction "1_1") (pintype "passive"))
      (node (ref "R15") (pin "2") (pinfunction "2_2") (pintype "passive"))
    )
    (net (code "25") (name "Net-(C21-Pad1)") (class "Default")
      (node (ref "C21") (pin "1") (pinfunction "1_1") (pintype "passive"))
      (node (ref "R14") (pin "1") (pinfunction "1_1") (pintype "passive"))
      (node (ref "R16") (pin "2") (pinfunction "2_2") (pintype "passive"))
    )
    (net (code "26") (name "Net-(D1-PadA)") (class "Default")
      (node (ref "D1") (pin "A") (pinfunction "A_A") (pintype "passive"))
      (node (ref "POWER") (pin "1") (pinfunction "1_1") (pintype "passive"))
      (node (ref "POWER") (pin "2") (pinfunction "2_2") (pintype "passive"))
    )
    (net (code "27") (name "Net-(D2-PadC)") (class "Default")
      (node (ref "D2") (pin "C") (pinfunction "C_C") (pintype "passive"))
      (node (ref "POWER") (pin "10") (pinfunction "10_10") (pintype "passive"))
      (node (ref "POWER") (pin "9") (pinfunction "9_9") (pintype "passive"))
    )
    (net (code "28") (name "Net-(IC5A--IN)") (class "Default")
      (node (ref "IC5") (pin "2") (pinfunction "-IN_2") (pintype "input"))
      (node (ref "R20") (pin "1") (pinfunction "1_1") (pintype "passive"))
      (node (ref "R21") (pin "1") (pinfunction "1_1") (pintype "passive"))
      (node (ref "R23") (pin "2") (pinfunction "2_2") (pintype "passive"))
    )
    (net (code "29") (name "Net-(IC5A-OUT)") (class "Default")
      (node (ref "IC5") (pin "1") (pinfunction "OUT_1") (pintype "output"))
      (node (ref "R22") (pin "2") (pinfunction "2_2") (pintype "passive"))
      (node (ref "R23") (pin "1") (pinfunction "1_1") (pintype "passive"))
    )
    (net (code "30") (name "Net-(IC5B-+IN)") (class "Default")
      (node (ref "C22") (pin "1") (pinfunction "1_1") (pintype "passive"))
      (node (ref "IC5") (pin "5") (pinfunction "+IN_5") (pintype "input"))
      (node (ref "R15") (pin "1") (pinfunction "1_1") (pintype "passive"))
    )
    (net (code "31") (name "Net-(IC5B--IN)") (class "Default")
      (node (ref "C19") (pin "2") (pinfunction "2_2") (pintype "passive"))
      (node (ref "IC5") (pin "6") (pinfunction "-IN_6") (pintype "input"))
      (node (ref "IC5") (pin "7") (pinfunction "OUT_7") (pintype "output"))
      (node (ref "R20") (pin "2") (pinfunction "2_2") (pintype "passive"))
    )
    (net (code "32") (name "Net-(IC6A-+IN)") (class "Default")
      (node (ref "C21") (pin "2") (pinfunction "2_2") (pintype "passive"))
      (node (ref "IC6") (pin "3") (pinfunction "+IN_3") (pintype "input"))
      (node (ref "IC6") (pin "6") (pinfunction "-IN_6") (pintype "input"))
      (node (ref "IC6") (pin "7") (pinfunction "OUT_7") (pintype "output"))
    )
    (net (code "33") (name "Net-(IC6A--IN)") (class "Default")
      (node (ref "IC6") (pin "2") (pinfunction "-IN_2") (pintype "input"))
      (node (ref "R25") (pin "2") (pinfunction "2_2") (pintype "passive"))
      (node (ref "R26") (pin "2") (pinfunction "2_2") (pintype "passive"))
    )
    (net (code "34") (name "Net-(IC6A-OUT)") (class "Default")
      (node (ref "IC6") (pin "1") (pinfunction "OUT_1") (pintype "output"))
      (node (ref "R24") (pin "2") (pinfunction "2_2") (pintype "passive"))
      (node (ref "R25") (pin "1") (pinfunction "1_1") (pintype "passive"))
    )
    (net (code "35") (name "Net-(IC6B-+IN)") (class "Default")
      (node (ref "C23") (pin "1") (pinfunction "1_1") (pintype "passive"))
      (node (ref "IC6") (pin "5") (pinfunction "+IN_5") (pintype "input"))
      (node (ref "R16") (pin "1") (pinfunction "1_1") (pintype "passive"))
    )
    (net (code "36") (name "Net-(IC8A--IN)") (class "Default")
      (node (ref "C31") (pin "1") (pinfunction "1_1") (pintype "passive"))
      (node (ref "IC8") (pin "2") (pinfunction "-IN_2") (pintype "input"))
      (node (ref "R37") (pin "2") (pinfunction "2_2") (pintype "passive"))
      (node (ref "R38") (pin "1") (pinfunction "1_1") (pintype "passive"))
      (node (ref "R39") (pin "1") (pinfunction "1_1") (pintype "passive"))
    )
    (net (code "37") (name "Net-(IC8B--IN)") (class "Default")
      (node (ref "C27") (pin "1") (pinfunction "1_1") (pintype "passive"))
      (node (ref "IC8") (pin "6") (pinfunction "-IN_6") (pintype "input"))
      (node (ref "R34") (pin "2") (pinfunction "2_2") (pintype "passive"))
      (node (ref "R35") (pin "1") (pinfunction "1_1") (pintype "passive"))
      (node (ref "R36") (pin "1") (pinfunction "1_1") (pintype "passive"))
    )
    (net (code "38") (name "Net-(IC9A--IN)") (class "Default")
      (node (ref "C32") (pin "1") (pinfunction "1_1") (pintype "passive"))
      (node (ref "IC9") (pin "2") (pinfunction "-IN_2") (pintype "input"))
      (node (ref "R40") (pin "2") (pinfunction "2_2") (pintype "passive"))
      (node (ref "R41") (pin "1") (pinfunction "1_1") (pintype "passive"))
      (node (ref "R42") (pin "1") (pinfunction "1_1") (pintype "passive"))
    )
    (net (code "39") (name "Net-(IC9B--IN)") (class "Default")
      (node (ref "C34") (pin "1") (pinfunction "1_1") (pintype "passive"))
      (node (ref "IC9") (pin "6") (pinfunction "-IN_6") (pintype "input"))
      (node (ref "R43") (pin "1") (pinfunction "1_1") (pintype "passive"))
      (node (ref "R44") (pin "1") (pinfunction "1_1") (pintype "passive"))
      (node (ref "R45") (pin "2") (pinfunction "2_2") (pintype "passive"))
    )
    (net (code "40") (name "Net-(IC9C--IN)") (class "Default")
      (node (ref "C28") (pin "1") (pinfunction "1_1") (pintype "passive"))
      (node (ref "IC9") (pin "9") (pinfunction "-IN_9") (pintype "input"))
      (node (ref "R31") (pin "1") (pinfunction "1_1") (pintype "passive"))
      (node (ref "R32") (pin "1") (pinfunction "1_1") (pintype "passive"))
      (node (ref "R33") (pin "2") (pinfunction "2_2") (pintype "passive"))
    )
    (net (code "41") (name "Net-(IC9D--IN)") (class "Default")
      (node (ref "C29") (pin "1") (pinfunction "1_1") (pintype "passive"))
      (node (ref "IC9") (pin "13") (pinfunction "-IN_13") (pintype "input"))
      (node (ref "R28") (pin "2") (pinfunction "2_2") (pintype "passive"))
      (node (ref "R29") (pin "1") (pinfunction "1_1") (pintype "passive"))
      (node (ref "R30") (pin "1") (pinfunction "1_1") (pintype "passive"))
    )
    (net (code "42") (name "Net-(J1-3)") (class "Default")
      (node (ref "J1") (pin "P3") (pinfunction "3_P3") (pintype "passive"))
      (node (ref "R42") (pin "2") (pinfunction "2_2") (pintype "passive"))
    )
    (net (code "43") (name "Net-(J2-3)") (class "Default")
      (node (ref "J2") (pin "P3") (pinfunction "3_P3") (pintype "passive"))
      (node (ref "R29") (pin "2") (pinfunction "2_2") (pintype "passive"))
    )
    (net (code "44") (name "Net-(J3-3)") (class "Default")
      (node (ref "J3") (pin "P3") (pinfunction "3_P3") (pintype "passive"))
      (node (ref "R32") (pin "2") (pinfunction "2_2") (pintype "passive"))
    )
    (net (code "45") (name "Net-(J4-3)") (class "Default")
      (node (ref "J4") (pin "P3") (pinfunction "3_P3") (pintype "passive"))
      (node (ref "R55") (pin "1") (pinfunction "1_1") (pintype "passive"))
    )
    (net (code "46") (name "Net-(J5-3)") (class "Default")
      (node (ref "J5") (pin "P3") (pinfunction "3_P3") (pintype "passive"))
      (node (ref "R56") (pin "1") (pinfunction "1_1") (pintype "passive"))
    )
    (net (code "47") (name "Net-(J6-3)") (class "Default")
      (node (ref "J6") (pin "P3") (pinfunction "3_P3") (pintype "passive"))
      (node (ref "R39") (pin "2") (pinfunction "2_2") (pintype "passive"))
    )
    (net (code "48") (name "Net-(J7-2)") (class "Default")
      (node (ref "J7") (pin "P2") (pinfunction "2_P2") (pintype "passive"))
      (node (ref "R46") (pin "1") (pinfunction "1_1") (pintype "passive"))
    )
    (net (code "49") (name "Net-(J7-3)") (class "Default")
      (node (ref "J7") (pin "P3") (pinfunction "3_P3") (pintype "passive"))
      (node (ref "R36") (pin "2") (pinfunction "2_2") (pintype "passive"))
    )
    (net (code "50") (name "Net-(J8-2)") (class "Default")
      (node (ref "J8") (pin "P2") (pinfunction "2_P2") (pintype "passive"))
      (node (ref "R60") (pin "2") (pinfunction "2_2") (pintype "passive"))
    )
    (net (code "51") (name "Net-(J8-3)") (class "Default")
      (node (ref "J8") (pin "P3") (pinfunction "3_P3") (pintype "passive"))
      (node (ref "R44") (pin "2") (pinfunction "2_2") (pintype "passive"))
    )
    (net (code "52") (name "Net-(J9-3)") (class "Default")
      (node (ref "J9") (pin "P3") (pinfunction "3_P3") (pintype "passive"))
      (node (ref "R54") (pin "1") (pinfunction "1_1") (pintype "passive"))
    )
    (net (code "53") (name "Net-(J10-3)") (class "Default")
      (node (ref "J10") (pin "P3") (pinfunction "3_P3") (pintype "passive"))
      (node (ref "Q5") (pin "C") (pinfunction "C_C") (pintype "passive"))
      (node (ref "R50") (pin "2") (pinfunction "2_2") (pintype "passive"))
      (node (ref "R51") (pin "1") (pinfunction "1_1") (pintype "passive"))
    )
    (net (code "54") (name "Net-(J11-3)") (class "Default")
      (node (ref "J11") (pin "P3") (pinfunction "3_P3") (pintype "passive"))
      (node (ref "Q6") (pin "C") (pinfunction "C_C") (pintype "passive"))
      (node (ref "R52") (pin "2") (pinfunction "2_2") (pintype "passive"))
      (node (ref "R53") (pin "1") (pinfunction "1_1") (pintype "passive"))
    )
    (net (code "55") (name "Net-(J12-3)") (class "Default")
      (node (ref "J12") (pin "P3") (pinfunction "3_P3") (pintype "passive"))
      (node (ref "R24") (pin "1") (pinfunction "1_1") (pintype "passive"))
    )
    (net (code "56") (name "Net-(J13-3)") (class "Default")
      (node (ref "J13") (pin "P3") (pinfunction "3_P3") (pintype "passive"))
      (node (ref "R22") (pin "1") (pinfunction "1_1") (pintype "passive"))
    )
    (net (code "57") (name "Net-(LED1-GRN)") (class "Default")
      (node (ref "LED1") (pin "1") (pinfunction "GRN_1") (pintype "bidirectional"))
      (node (ref "R2") (pin "2") (pinfunction "2_2") (pintype "passive"))
    )
    (net (code "58") (name "Net-(LED1-RED)") (class "Default")
      (node (ref "LED1") (pin "3") (pinfunction "RED_3") (pintype "bidirectional"))
      (node (ref "R3") (pin "2") (pinfunction "2_2") (pintype "passive"))
    )
    (net (code "59") (name "Net-(LED2-GRN)") (class "Default")
      (node (ref "LED2") (pin "1") (pinfunction "GRN_1") (pintype "bidirectional"))
      (node (ref "R4") (pin "2") (pinfunction "2_2") (pintype "passive"))
    )
    (net (code "60") (name "Net-(LED2-RED)") (class "Default")
      (node (ref "LED2") (pin "3") (pinfunction "RED_3") (pintype "bidirectional"))
      (node (ref "R7") (pin "2") (pinfunction "2_2") (pintype "passive"))
    )
    (net (code "61") (name "Net-(LED3-GRN)") (class "Default")
      (node (ref "LED3") (pin "1") (pinfunction "GRN_1") (pintype "bidirectional"))
      (node (ref "R9") (pin "2") (pinfunction "2_2") (pintype "passive"))
    )
    (net (code "62") (name "Net-(LED3-RED)") (class "Default")
      (node (ref "LED3") (pin "3") (pinfunction "RED_3") (pintype "bidirectional"))
      (node (ref "R10") (pin "2") (pinfunction "2_2") (pintype "passive"))
    )
    (net (code "63") (name "Net-(Q2-PadB)") (class "Default")
      (node (ref "Q2") (pin "B") (pinfunction "B_B") (pintype "passive"))
      (node (ref "R55") (pin "2") (pinfunction "2_2") (pintype "passive"))
    )
    (net (code "64") (name "Net-(Q3-PadB)") (class "Default")
      (node (ref "Q3") (pin "B") (pinfunction "B_B") (pintype "passive"))
      (node (ref "R54") (pin "2") (pinfunction "2_2") (pintype "passive"))
    )
    (net (code "65") (name "Net-(Q4-PadB)") (class "Default")
      (node (ref "Q4") (pin "B") (pinfunction "B_B") (pintype "passive"))
      (node (ref "R56") (pin "2") (pinfunction "2_2") (pintype "passive"))
    )
    (net (code "66") (name "Net-(Q5-PadB)") (class "Default")
      (node (ref "Q5") (pin "B") (pinfunction "B_B") (pintype "passive"))
      (node (ref "R57") (pin "2") (pinfunction "2_2") (pintype "passive"))
    )
    (net (code "67") (name "Net-(Q6-PadB)") (class "Default")
      (node (ref "Q6") (pin "B") (pinfunction "B_B") (pintype "passive"))
      (node (ref "R58") (pin "2") (pinfunction "2_2") (pintype "passive"))
    )
    (net (code "68") (name "Net-(R5-E)") (class "Default")
      (node (ref "R5") (pin "P$1") (pinfunction "E_P$1") (pintype "passive"))
      (node (ref "R8") (pin "2") (pinfunction "2_2") (pintype "passive"))
    )
    (net (code "69") (name "Net-(R5-S)") (class "Default")
      (node (ref "R38") (pin "2") (pinfunction "2_2") (pintype "passive"))
      (node (ref "R5") (pin "P$2") (pinfunction "S_P$2") (pintype "passive"))
    )
    (net (code "70") (name "Net-(R17-S)") (class "Default")
      (node (ref "R17") (pin "P$2") (pinfunction "S_P$2") (pintype "passive"))
      (node (ref "R41") (pin "2") (pinfunction "2_2") (pintype "passive"))
    )
    (net (code "71") (name "Net-(R18-S)") (class "Default")
      (node (ref "R18") (pin "P$2") (pinfunction "S_P$2") (pintype "passive"))
      (node (ref "R30") (pin "2") (pinfunction "2_2") (pintype "passive"))
    )
    (net (code "72") (name "Net-(R19-S)") (class "Default")
      (node (ref "R19") (pin "P$2") (pinfunction "S_P$2") (pintype "passive"))
      (node (ref "R31") (pin "2") (pinfunction "2_2") (pintype "passive"))
    )
    (net (code "73") (name "Net-(R59-A)") (class "Default")
      (node (ref "R21") (pin "2") (pinfunction "2_2") (pintype "passive"))
      (node (ref "R59") (pin "1") (pinfunction "A_1") (pintype "passive"))
    )
    (net (code "74") (name "Net-(UC1-PB4{slash}NJTRST)") (class "Default")
      (node (ref "R2") (pin "1") (pinfunction "1_1") (pintype "passive"))
      (node (ref "UC1") (pin "40") (pinfunction "PB4/NJTRST_40") (pintype "bidirectional"))
    )
    (net (code "75") (name "Net-(UC1-PB5{slash}I2C1_SMBA)") (class "Default")
      (node (ref "R3") (pin "1") (pinfunction "1_1") (pintype "passive"))
      (node (ref "UC1") (pin "41") (pinfunction "PB5/I2C1_SMBA_41") (pintype "input"))
    )
    (net (code "76") (name "Net-(UC1-PB6{slash}I2C1_SCL{slash}TIM4_CH1)") (class "Default")
      (node (ref "R4") (pin "1") (pinfunction "1_1") (pintype "passive"))
      (node (ref "UC1") (pin "42") (pinfunction "PB6/I2C1_SCL/TIM4_CH1_42") (pintype "input"))
    )
    (net (code "77") (name "Net-(UC1-PB7{slash}I2C1_SDA{slash}TIM4_CH2)") (class "Default")
      (node (ref "R7") (pin "1") (pinfunction "1_1") (pintype "passive"))
      (node (ref "UC1") (pin "43") (pinfunction "PB7/I2C1_SDA/TIM4_CH2_43") (pintype "bidirectional"))
    )
    (net (code "78") (name "Net-(UC1-PB8{slash}TIM4_CH3)") (class "Default")
      (node (ref "R9") (pin "1") (pinfunction "1_1") (pintype "passive"))
      (node (ref "UC1") (pin "45") (pinfunction "PB8/TIM4_CH3_45") (pintype "bidirectional"))
    )
    (net (code "79") (name "Net-(UC1-PB9{slash}TIM4_CH4)") (class "Default")
      (node (ref "R10") (pin "1") (pinfunction "1_1") (pintype "passive"))
      (node (ref "UC1") (pin "46") (pinfunction "PB9/TIM4_CH4_46") (pintype "input"))
    )
    (net (code "80") (name "Net-(UC1-PD0-OSC_IN)") (class "Default")
      (node (ref "C2") (pin "2") (pinfunction "2_2") (pintype "passive"))
      (node (ref "Q1") (pin "2") (pinfunction "2_2") (pintype "passive"))
      (node (ref "UC1") (pin "5") (pinfunction "PD0-OSC_IN_5") (pintype "input"))
    )
    (net (code "81") (name "Net-(UC1-PD1-OSC_OUT)") (class "Default")
      (node (ref "C17") (pin "2") (pinfunction "2_2") (pintype "passive"))
      (node (ref "Q1") (pin "1") (pinfunction "1_1") (pintype "passive"))
      (node (ref "UC1") (pin "6") (pinfunction "PD1-OSC_OUT_6") (pintype "input"))
    )
    (net (code "82") (name "PROC_ADC") (class "Default")
      (node (ref "C28") (pin "2") (pinfunction "2_2") (pintype "passive"))
      (node (ref "IC9") (pin "8") (pinfunction "OUT_8") (pintype "output"))
      (node (ref "R33") (pin "1") (pinfunction "1_1") (pintype "passive"))
      (node (ref "UC1") (pin "17") (pinfunction "PA7/SPI1_MOSI/ADC12_IN7/TIM3_CH2_17") (pintype "bidirectional"))
    )
    (net (code "83") (name "RANGE_SW") (class "Default")
      (node (ref "SW4") (pin "3") (pinfunction "S_3") (pintype "passive"))
      (node (ref "SW4") (pin "4") (pinfunction "S1_4") (pintype "passive"))
      (node (ref "UC1") (pin "11") (pinfunction "PA1/USART2_RTS/ADC12_IN1/TIM2_CH2_11") (pintype "bidirectional"))
    )
    (net (code "84") (name "RESET") (class "Default")
      (node (ref "JTAG") (pin "10") (pinfunction "10_10") (pintype "passive"))
      (node (ref "UC1") (pin "7") (pinfunction "NRST_7") (pintype "input"))
    )
    (net (code "85") (name "RX") (class "Default")
      (node (ref "UC1") (pin "31") (pinfunction "PA10/USART1_RX/TIM1_CH3_31") (pintype "bidirectional"))
    )
    (net (code "86") (name "SHAPE_ADC") (class "Default")
      (node (ref "C32") (pin "2") (pinfunction "2_2") (pintype "passive"))
      (node (ref "IC9") (pin "1") (pinfunction "OUT_1") (pintype "output"))
      (node (ref "R40") (pin "1") (pinfunction "1_1") (pintype "passive"))
      (node (ref "UC1") (pin "15") (pinfunction "PA5/SPI1_SCK/ADC12_IN5_15") (pintype "bidirectional"))
    )
    (net (code "87") (name "START") (class "Default")
      (node (ref "Q2") (pin "C") (pinfunction "C_C") (pintype "passive"))
      (node (ref "R47") (pin "1") (pinfunction "1_1") (pintype "passive"))
      (node (ref "UC1") (pin "22") (pinfunction "PB11/I2C2_SDA/USART3_RX_22") (pintype "input"))
    )
    (net (code "88") (name "TX") (class "Default")
      (node (ref "UC1") (pin "30") (pinfunction "PA9/USART1_TX/TIM1_CH2_30") (pintype "input"))
    )
    (net (code "89") (name "UNI") (class "Default")
      (node (ref "IC4") (pin "4") (pinfunction "OUTA_4") (pintype "output"))
      (node (ref "R14") (pin "2") (pinfunction "2_2") (pintype "passive"))
    )
    (net (code "90") (name "VCC") (class "Default")
      (node (ref "C18") (pin "1") (pinfunction "1_1") (pintype "passive"))
      (node (ref "C20") (pin "1") (pinfunction "1_1") (pintype "passive"))
      (node (ref "C3") (pin "+") (pinfunction "+_+") (pintype "passive"))
      (node (ref "C8") (pin "+") (pinfunction "+_+") (pintype "passive"))
      (node (ref "D1") (pin "C") (pinfunction "C_C") (pintype "passive"))
      (node (ref "IC1") (pin "3") (pinfunction "VIN_3") (pintype "input"))
      (node (ref "IC3") (pin "3") (pinfunction "VIN_3") (pintype "input"))
      (node (ref "IC5") (pin "8") (pinfunction "V+_8") (pintype "power_in"))
      (node (ref "IC6") (pin "8") (pinfunction "V+_8") (pintype "power_in"))
      (node (ref "R51") (pin "2") (pinfunction "2_2") (pintype "passive"))
      (node (ref "R53") (pin "2") (pinfunction "2_2") (pintype "passive"))
      (node (ref "R60") (pin "1") (pinfunction "1_1") (pintype "passive"))
    )
    (net (code "91") (name "VEE") (class "Default")
      (node (ref "C10") (pin "-") (pinfunction "-_-") (pintype "passive"))
      (node (ref "C24") (pin "2") (pinfunction "2_2") (pintype "passive"))
      (node (ref "C25") (pin "2") (pinfunction "2_2") (pintype "passive"))
      (node (ref "D2") (pin "A") (pinfunction "A_A") (pintype "passive"))
      (node (ref "IC5") (pin "4") (pinfunction "V-_4") (pintype "power_in"))
      (node (ref "IC6") (pin "4") (pinfunction "V-_4") (pintype "power_in"))
      (node (ref "R27") (pin "1") (pinfunction "1_1") (pintype "passive"))
    )
    (net (code "92") (name "VOCT_ADC") (class "Default")
      (node (ref "C31") (pin "2") (pinfunction "2_2") (pintype "passive"))
      (node (ref "IC8") (pin "1") (pinfunction "OUT_1") (pintype "output"))
      (node (ref "R37") (pin "1") (pinfunction "1_1") (pintype "passive"))
      (node (ref "UC1") (pin "13") (pinfunction "PA3/USART2_RX/ADC12_IN3/TIM2_CH4_13") (pintype "bidirectional"))
    )
    (net (code "93") (name "unconnected-(J1-2-PadP2)") (class "Default")
      (node (ref "J1") (pin "P2") (pinfunction "2_P2") (pintype "passive"))
    )
    (net (code "94") (name "unconnected-(J2-2-PadP2)") (class "Default")
      (node (ref "J2") (pin "P2") (pinfunction "2_P2") (pintype "passive"))
    )
    (net (code "95") (name "unconnected-(J3-2-PadP2)") (class "Default")
      (node (ref "J3") (pin "P2") (pinfunction "2_P2") (pintype "passive"))
    )
    (net (code "96") (name "unconnected-(J6-2-PadP2)") (class "Default")
      (node (ref "J6") (pin "P2") (pinfunction "2_P2") (pintype "passive"))
    )
    (net (code "97") (name "unconnected-(J10-2-PadP2)") (class "Default")
      (node (ref "J10") (pin "P2") (pinfunction "2_P2") (pintype "passive"))
    )
    (net (code "98") (name "unconnected-(J11-2-PadP2)") (class "Default")
      (node (ref "J11") (pin "P2") (pinfunction "2_P2") (pintype "passive"))
    )
    (net (code "99") (name "unconnected-(J12-2-PadP2)") (class "Default")
      (node (ref "J12") (pin "P2") (pinfunction "2_P2") (pintype "passive"))
    )
    (net (code "100") (name "unconnected-(J13-2-PadP2)") (class "Default")
      (node (ref "J13") (pin "P2") (pinfunction "2_P2") (pintype "passive"))
    )
    (net (code "101") (name "unconnected-(JTAG-Pad7)") (class "Default")
      (node (ref "JTAG") (pin "7") (pinfunction "7_7") (pintype "passive"))
    )
    (net (code "102") (name "unconnected-(UC1-PA8{slash}USART1_CK{slash}TIM1_CH1{slash}MCO-Pad29)") (class "Default")
      (node (ref "UC1") (pin "29") (pinfunction "PA8/USART1_CK/TIM1_CH1/MCO_29") (pintype "bidirectional"))
    )
    (net (code "103") (name "unconnected-(UC1-PB14{slash}SPI2_MISO{slash}USART3_RTS{slash}TIM1_CH2N-Pad27)") (class "Default")
      (node (ref "UC1") (pin "27") (pinfunction "PB14/SPI2_MISO/USART3_RTS/TIM1_CH2N_27") (pintype "input"))
    )
    (net (code "104") (name "unconnected-(UC1-PC13-TAMPER-RTC-Pad2)") (class "Default")
      (node (ref "UC1") (pin "2") (pinfunction "PC13-TAMPER-RTC_2") (pintype "input"))
    )
    (net (code "105") (name "unconnected-(UC1-PC14-OSC32_IN-Pad3)") (class "Default")
      (node (ref "UC1") (pin "3") (pinfunction "PC14-OSC32_IN_3") (pintype "input"))
    )
    (net (code "106") (name "unconnected-(UC1-PC15-OSC32_OUT-Pad4)") (class "Default")
      (node (ref "UC1") (pin "4") (pinfunction "PC15-OSC32_OUT_4") (pintype "input"))
    )
  )
)
